# TSL2671.net
KiCad netlist of a schematic drawn in EAGLE
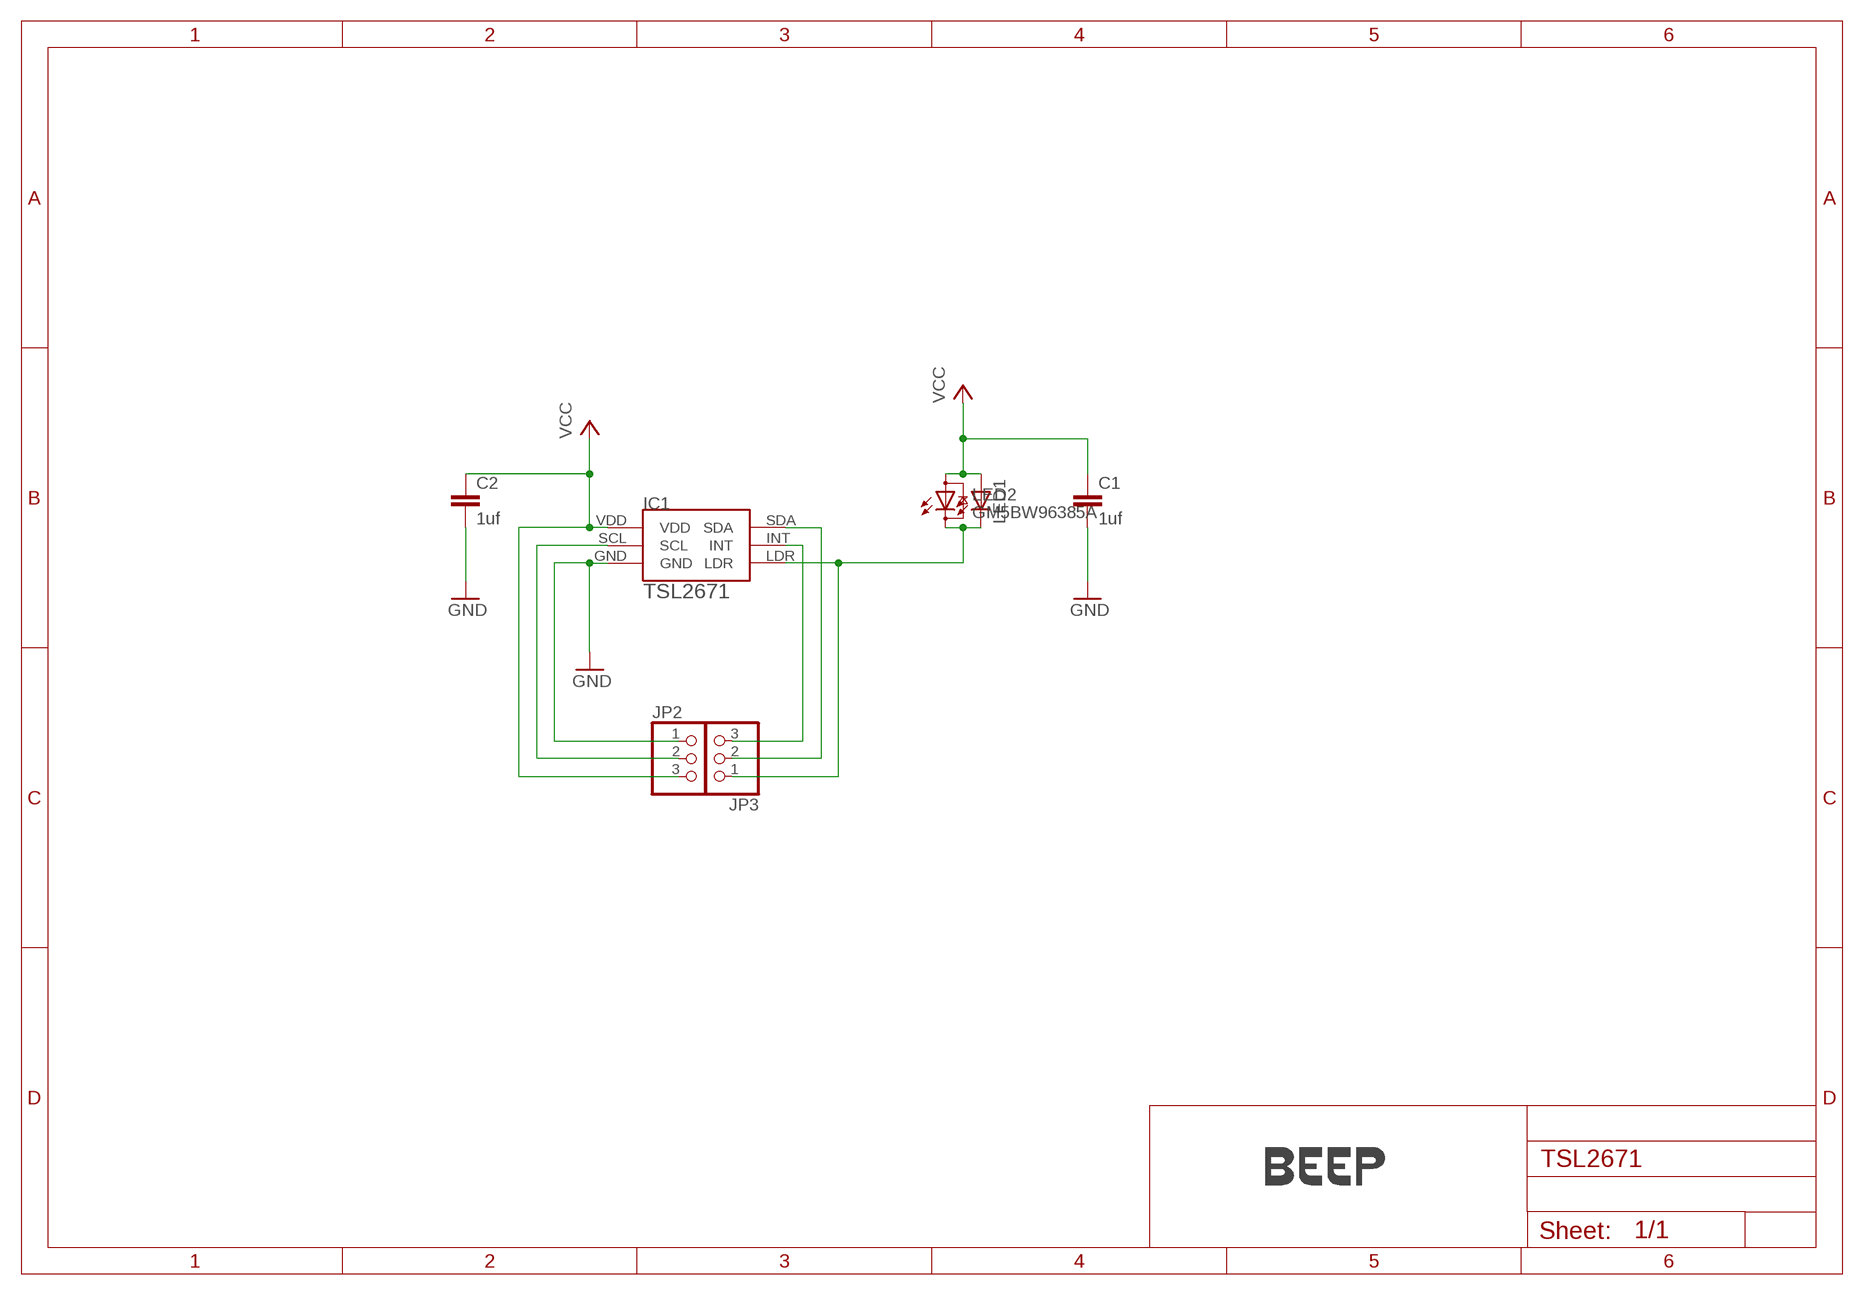
[diagram p0: schematic, sheet 1]

(export (version "E")
  (design (tool "Eeschema 10.0.6"))
  (components
    (comp (ref "C1")
      (value "1uf")
      (footprint "eagle-import:C025-025X050")
      (libsource (lib "eagle-import") (part "C-EU025-025X050"))
    )
    (comp (ref "C2")
      (value "1uf")
      (footprint "eagle-import:C1206K")
      (libsource (lib "eagle-import") (part "C-EUC1206K"))
    )
    (comp (ref "IC1")
      (value "TSL2671")
      (footprint "eagle-import:TSL2671")
      (libsource (lib "eagle-import") (part "TSL2671"))
    )
    (comp (ref "JP2")
      (value "PINHD-1X3")
      (footprint "eagle-import:1X03")
      (libsource (lib "eagle-import") (part "PINHD-1X3"))
    )
    (comp (ref "JP3")
      (value "PINHD-1X3")
      (footprint "eagle-import:1X03")
      (libsource (lib "eagle-import") (part "PINHD-1X3"))
    )
    (comp (ref "LED1")
      (value "LED5MM")
      (footprint "eagle-import:LED5MM")
      (libsource (lib "eagle-import") (part "LED5MM"))
    )
    (comp (ref "LED2")
      (value "GM5BW96385A")
      (footprint "eagle-import:GM5BW96385A")
      (libsource (lib "eagle-import") (part "GM5BW96385A"))
    )
    (comp (ref "U$1")
      (value "LOGO-COPPER4")
      (footprint "eagle-import:COPPER4")
      (libsource (lib "eagle-import") (part "LOGO-COPPER4"))
    )
  )
  (nets
    (net (code "1") (name "GND") (class "Default")
      (node (ref "C1") (pin "2") (pinfunction "2_2") (pintype "passive"))
      (node (ref "C2") (pin "2") (pinfunction "2_2") (pintype "passive"))
      (node (ref "IC1") (pin "GND") (pinfunction "GND_GND") (pintype "power_in"))
      (node (ref "JP2") (pin "1") (pinfunction "1_1") (pintype "passive"))
    )
    (net (code "2") (name "Net-(IC1-PadINT)") (class "Default")
      (node (ref "IC1") (pin "INT") (pinfunction "INT_INT") (pintype "output"))
      (node (ref "JP3") (pin "3") (pinfunction "3_3") (pintype "passive"))
    )
    (net (code "3") (name "Net-(IC1-PadSCL)") (class "Default")
      (node (ref "IC1") (pin "SCL") (pinfunction "SCL_SCL") (pintype "bidirectional"))
      (node (ref "JP2") (pin "2") (pinfunction "2_2") (pintype "passive"))
    )
    (net (code "4") (name "Net-(IC1-PadSDA)") (class "Default")
      (node (ref "IC1") (pin "SDA") (pinfunction "SDA_SDA") (pintype "bidirectional"))
      (node (ref "JP3") (pin "2") (pinfunction "2_2") (pintype "passive"))
    )
    (net (code "5") (name "Net-(LED1-C)") (class "Default")
      (node (ref "IC1") (pin "LDR") (pinfunction "LDR_LDR") (pintype "power_in"))
      (node (ref "JP3") (pin "1") (pinfunction "1_1") (pintype "passive"))
      (node (ref "LED1") (pin "K") (pinfunction "C_K") (pintype "passive"))
      (node (ref "LED2") (pin "C") (pinfunction "C_C") (pintype "passive"))
    )
    (net (code "6") (name "VCC") (class "Default")
      (node (ref "C1") (pin "1") (pinfunction "1_1") (pintype "passive"))
      (node (ref "C2") (pin "1") (pinfunction "1_1") (pintype "passive"))
      (node (ref "IC1") (pin "VDD") (pinfunction "VDD_VDD") (pintype "power_in"))
      (node (ref "JP2") (pin "3") (pinfunction "3_3") (pintype "passive"))
      (node (ref "LED1") (pin "A") (pinfunction "A_A") (pintype "passive"))
      (node (ref "LED2") (pin "A") (pinfunction "A_A") (pintype "passive"))
    )
  )
)
